# detached-display-board.net
KiCad netlist of a schematic drawn in EAGLE
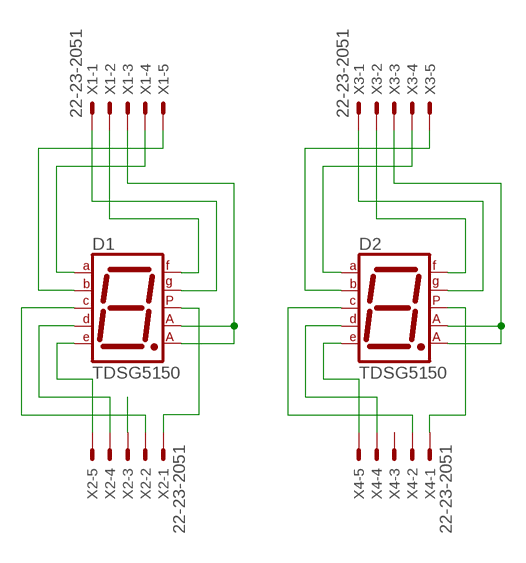
[diagram p0: schematic, sheet 1]

(export (version "E")
  (design (tool "Eeschema 10.0.6"))
  (components
    (comp (ref "D1")
      (value "TDSG5150")
      (footprint "eagle-import:7SEG-13")
      (libsource (lib "eagle-import") (part "7SEG-CA"))
    )
    (comp (ref "D2")
      (value "TDSG5150")
      (footprint "eagle-import:7SEG-13")
      (libsource (lib "eagle-import") (part "7SEG-CA"))
    )
    (comp (ref "X1")
      (value "22-23-2051")
      (footprint "eagle-import:22-23-2051")
      (fields (field (name "MF") "MOLEX"))
      (libsource (lib "eagle-import") (part "22-23-2051"))
    )
    (comp (ref "X2")
      (value "22-23-2051")
      (footprint "eagle-import:22-23-2051")
      (fields (field (name "MF") "MOLEX"))
      (libsource (lib "eagle-import") (part "22-23-2051"))
    )
    (comp (ref "X3")
      (value "22-23-2051")
      (footprint "eagle-import:22-23-2051")
      (fields (field (name "MF") "MOLEX"))
      (libsource (lib "eagle-import") (part "22-23-2051"))
    )
    (comp (ref "X4")
      (value "22-23-2051")
      (footprint "eagle-import:22-23-2051")
      (fields (field (name "MF") "MOLEX"))
      (libsource (lib "eagle-import") (part "22-23-2051"))
    )
  )
  (nets
    (net (code "1") (name "Net-(D1-A)") (class "Default")
      (node (ref "D1") (pin "7") (pinfunction "A_7") (pintype "passive"))
      (node (ref "X1") (pin "4") (pinfunction "S_4") (pintype "passive"))
    )
    (net (code "2") (name "Net-(D1-B)") (class "Default")
      (node (ref "D1") (pin "6") (pinfunction "B_6") (pintype "passive"))
      (node (ref "X1") (pin "5") (pinfunction "S_5") (pintype "passive"))
    )
    (net (code "3") (name "Net-(D1-C)") (class "Default")
      (node (ref "D1") (pin "4") (pinfunction "C_4") (pintype "passive"))
      (node (ref "X2") (pin "2") (pinfunction "S_2") (pintype "passive"))
    )
    (net (code "4") (name "Net-(D1-CA1)") (class "Default")
      (node (ref "D1") (pin "3") (pinfunction "CA1_3") (pintype "passive"))
      (node (ref "D1") (pin "8") (pinfunction "CA2_8") (pintype "passive"))
      (node (ref "X1") (pin "3") (pinfunction "S_3") (pintype "passive"))
    )
    (net (code "5") (name "Net-(D1-D)") (class "Default")
      (node (ref "D1") (pin "2") (pinfunction "D_2") (pintype "passive"))
      (node (ref "X2") (pin "4") (pinfunction "S_4") (pintype "passive"))
    )
    (net (code "6") (name "Net-(D1-DP)") (class "Default")
      (node (ref "D1") (pin "5") (pinfunction "DP_5") (pintype "passive"))
      (node (ref "X2") (pin "1") (pinfunction "S_1") (pintype "passive"))
    )
    (net (code "7") (name "Net-(D1-E)") (class "Default")
      (node (ref "D1") (pin "1") (pinfunction "E_1") (pintype "passive"))
      (node (ref "X2") (pin "5") (pinfunction "S_5") (pintype "passive"))
    )
    (net (code "8") (name "Net-(D1-F)") (class "Default")
      (node (ref "D1") (pin "9") (pinfunction "F_9") (pintype "passive"))
      (node (ref "X1") (pin "2") (pinfunction "S_2") (pintype "passive"))
    )
    (net (code "9") (name "Net-(D1-G)") (class "Default")
      (node (ref "D1") (pin "10") (pinfunction "G_10") (pintype "passive"))
      (node (ref "X1") (pin "1") (pinfunction "S_1") (pintype "passive"))
    )
    (net (code "10") (name "Net-(D2-A)") (class "Default")
      (node (ref "D2") (pin "7") (pinfunction "A_7") (pintype "passive"))
      (node (ref "X3") (pin "4") (pinfunction "S_4") (pintype "passive"))
    )
    (net (code "11") (name "Net-(D2-B)") (class "Default")
      (node (ref "D2") (pin "6") (pinfunction "B_6") (pintype "passive"))
      (node (ref "X3") (pin "5") (pinfunction "S_5") (pintype "passive"))
    )
    (net (code "12") (name "Net-(D2-C)") (class "Default")
      (node (ref "D2") (pin "4") (pinfunction "C_4") (pintype "passive"))
      (node (ref "X4") (pin "2") (pinfunction "S_2") (pintype "passive"))
    )
    (net (code "13") (name "Net-(D2-CA1)") (class "Default")
      (node (ref "D2") (pin "3") (pinfunction "CA1_3") (pintype "passive"))
      (node (ref "D2") (pin "8") (pinfunction "CA2_8") (pintype "passive"))
      (node (ref "X3") (pin "3") (pinfunction "S_3") (pintype "passive"))
    )
    (net (code "14") (name "Net-(D2-D)") (class "Default")
      (node (ref "D2") (pin "2") (pinfunction "D_2") (pintype "passive"))
      (node (ref "X4") (pin "4") (pinfunction "S_4") (pintype "passive"))
    )
    (net (code "15") (name "Net-(D2-DP)") (class "Default")
      (node (ref "D2") (pin "5") (pinfunction "DP_5") (pintype "passive"))
      (node (ref "X4") (pin "1") (pinfunction "S_1") (pintype "passive"))
    )
    (net (code "16") (name "Net-(D2-E)") (class "Default")
      (node (ref "D2") (pin "1") (pinfunction "E_1") (pintype "passive"))
      (node (ref "X4") (pin "5") (pinfunction "S_5") (pintype "passive"))
    )
    (net (code "17") (name "Net-(D2-F)") (class "Default")
      (node (ref "D2") (pin "9") (pinfunction "F_9") (pintype "passive"))
      (node (ref "X3") (pin "2") (pinfunction "S_2") (pintype "passive"))
    )
    (net (code "18") (name "Net-(D2-G)") (class "Default")
      (node (ref "D2") (pin "10") (pinfunction "G_10") (pintype "passive"))
      (node (ref "X3") (pin "1") (pinfunction "S_1") (pintype "passive"))
    )
    (net (code "19") (name "unconnected-(X2C-S-Pad3)") (class "Default")
      (node (ref "X2") (pin "3") (pinfunction "S_3") (pintype "passive"))
    )
    (net (code "20") (name "unconnected-(X4C-S-Pad3)") (class "Default")
      (node (ref "X4") (pin "3") (pinfunction "S_3") (pintype "passive"))
    )
  )
)
